# 1591XXM-RS485_to_Neopixel_with_RJ45.net
KiCad netlist of a schematic drawn in EAGLE
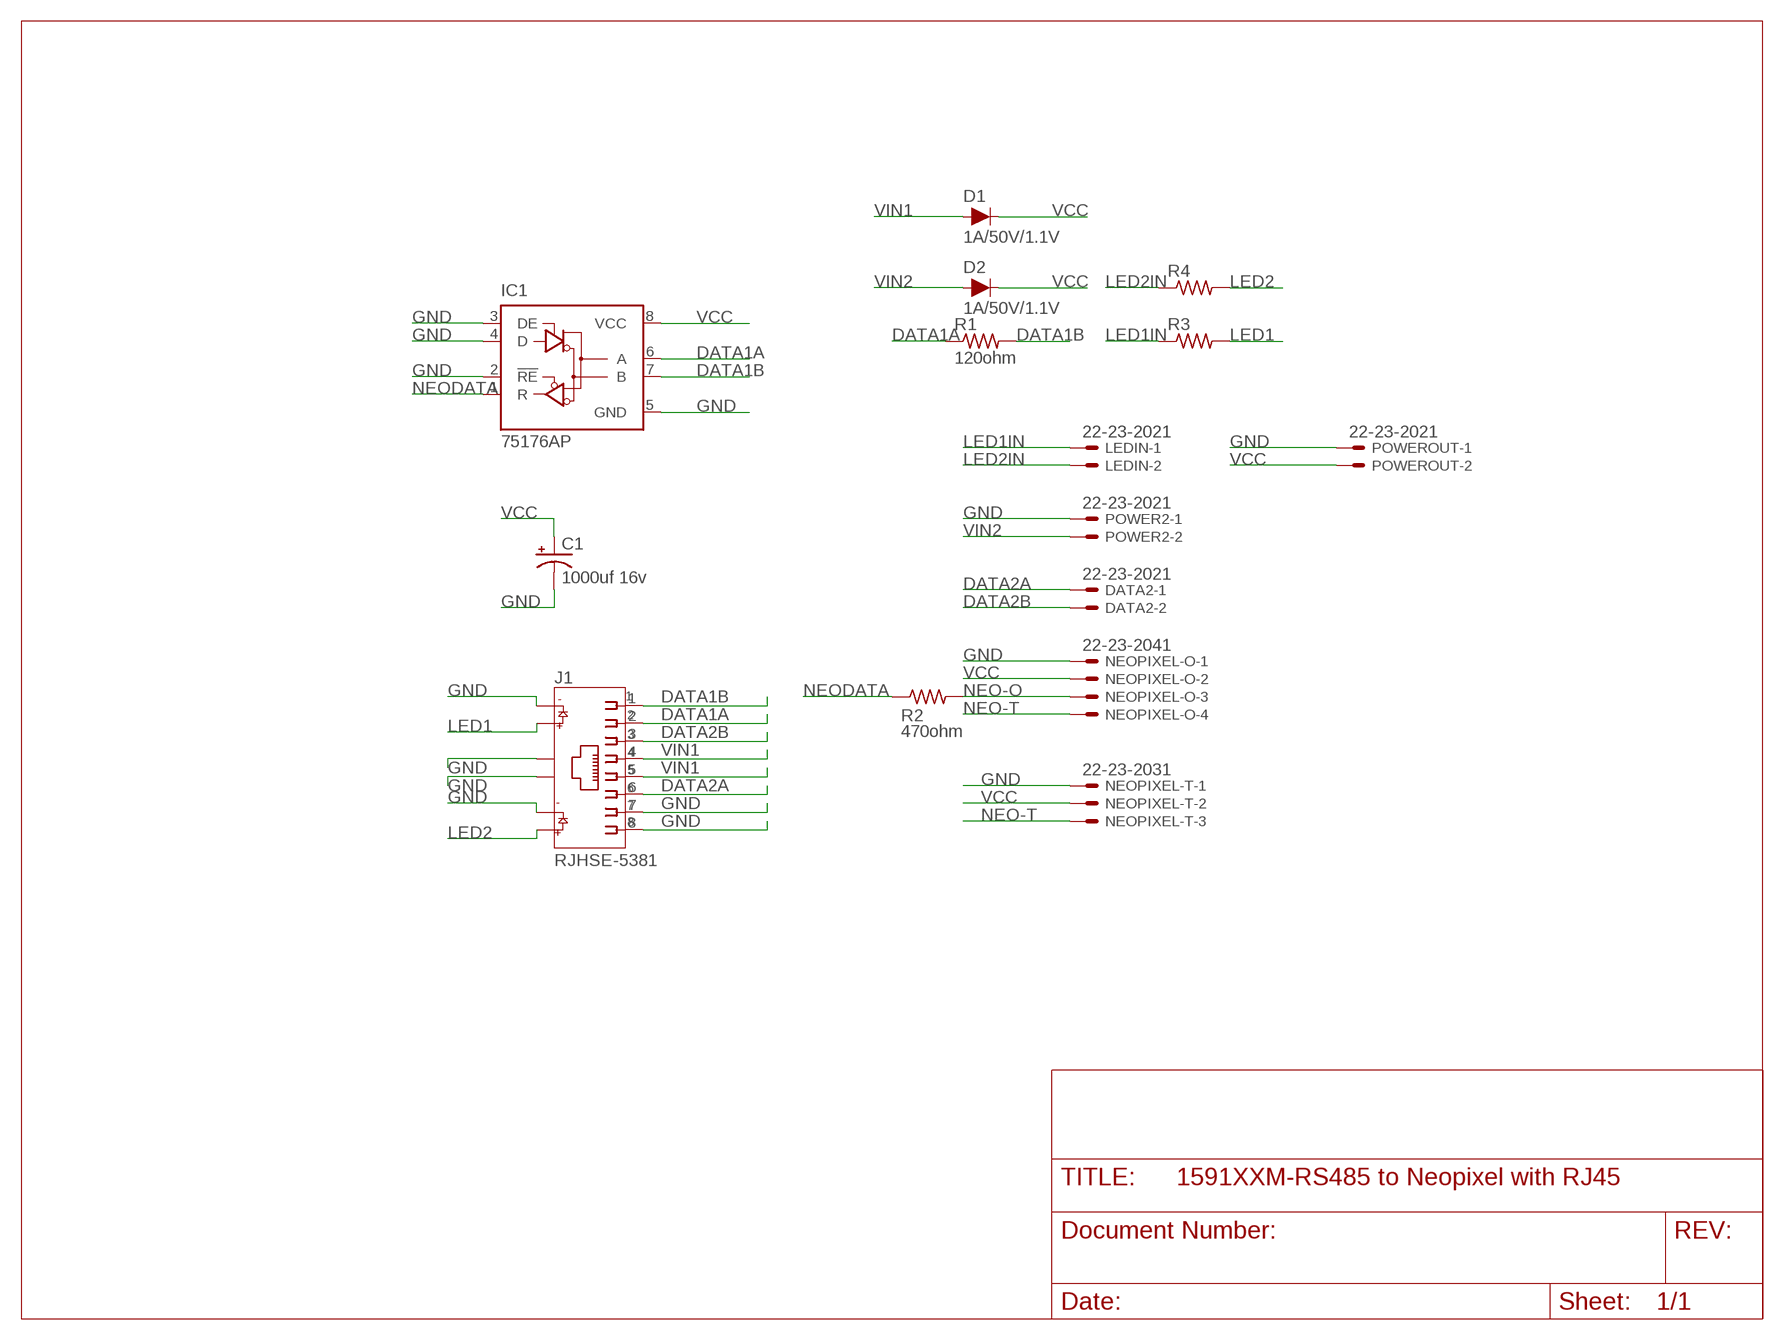
[diagram p0: schematic, sheet 1]

(export (version "E")
  (design (tool "Eeschema 10.0.6"))
  (components
    (comp (ref "C1")
      (value "1000uf 16v")
      (footprint "eagle-import:CPOL-RADIAL-5MM-10MM")
      (libsource (lib "eagle-import") (part "1000UF-RADIAL-5MM-25V-20%"))
    )
    (comp (ref "D1")
      (value "1A/50V/1.1V")
      (footprint "eagle-import:DIODE-1N4001")
      (libsource (lib "eagle-import") (part "DIODE-PTH"))
    )
    (comp (ref "D2")
      (value "1A/50V/1.1V")
      (footprint "eagle-import:DIODE-1N4001")
      (libsource (lib "eagle-import") (part "DIODE-PTH"))
    )
    (comp (ref "DATA2")
      (value "22-23-2021")
      (footprint "eagle-import:22-23-2021")
      (fields (field (name "MF") "MOLEX"))
      (libsource (lib "eagle-import") (part "22-23-2021"))
    )
    (comp (ref "IC1")
      (value "75176AP")
      (footprint "eagle-import:DIL08")
      (libsource (lib "eagle-import") (part "75176AP"))
    )
    (comp (ref "J1")
      (value "RJHSE-5381")
      (footprint "eagle-import:AMPHENOL_RJHSE-5381")
      (fields (field (name "MF") "Amphenol ICC"))
      (libsource (lib "eagle-import") (part "RJHSE-5381"))
    )
    (comp (ref "LEDIN")
      (value "22-23-2021")
      (footprint "eagle-import:22-23-2021")
      (fields (field (name "MF") "MOLEX"))
      (libsource (lib "eagle-import") (part "22-23-2021"))
    )
    (comp (ref "NEOPIXEL-O")
      (value "22-23-2041")
      (footprint "eagle-import:22-23-2041")
      (fields (field (name "MF") "MOLEX"))
      (libsource (lib "eagle-import") (part "22-23-2041"))
    )
    (comp (ref "NEOPIXEL-T")
      (value "22-23-2031")
      (footprint "eagle-import:22-23-2031")
      (fields (field (name "MF") "MOLEX"))
      (libsource (lib "eagle-import") (part "22-23-2031"))
    )
    (comp (ref "POWER2")
      (value "22-23-2021")
      (footprint "eagle-import:22-23-2021")
      (fields (field (name "MF") "MOLEX"))
      (libsource (lib "eagle-import") (part "22-23-2021"))
    )
    (comp (ref "POWEROUT")
      (value "22-23-2021")
      (footprint "eagle-import:22-23-2021")
      (fields (field (name "MF") "MOLEX"))
      (libsource (lib "eagle-import") (part "22-23-2021"))
    )
    (comp (ref "R1")
      (value "120ohm")
      (footprint "eagle-import:0207_10")
      (libsource (lib "eagle-import") (part "R-US_0207/10"))
    )
    (comp (ref "R2")
      (value "470ohm")
      (footprint "eagle-import:0207_10")
      (libsource (lib "eagle-import") (part "R-US_0207/10"))
    )
    (comp (ref "R3")
      (value "R-US_0207/10")
      (footprint "eagle-import:0207_10")
      (libsource (lib "eagle-import") (part "R-US_0207/10"))
    )
    (comp (ref "R4")
      (value "R-US_0207/10")
      (footprint "eagle-import:0207_10")
      (libsource (lib "eagle-import") (part "R-US_0207/10"))
    )
  )
  (nets
    (net (code "1") (name "/DATA1A") (class "Default")
      (node (ref "IC1") (pin "6") (pinfunction "A_6") (pintype "output"))
      (node (ref "J1") (pin "2") (pinfunction "2_2") (pintype "passive"))
      (node (ref "R1") (pin "1") (pinfunction "1_1") (pintype "passive"))
    )
    (net (code "2") (name "/DATA1B") (class "Default")
      (node (ref "IC1") (pin "7") (pinfunction "B_7") (pintype "output"))
      (node (ref "J1") (pin "1") (pinfunction "1_1") (pintype "passive"))
      (node (ref "R1") (pin "2") (pinfunction "2_2") (pintype "passive"))
    )
    (net (code "3") (name "/DATA2A") (class "Default")
      (node (ref "DATA2") (pin "1") (pinfunction "S_1") (pintype "passive"))
      (node (ref "J1") (pin "6") (pinfunction "6_6") (pintype "passive"))
    )
    (net (code "4") (name "/DATA2B") (class "Default")
      (node (ref "DATA2") (pin "2") (pinfunction "S_2") (pintype "passive"))
      (node (ref "J1") (pin "3") (pinfunction "3_3") (pintype "passive"))
    )
    (net (code "5") (name "/GND") (class "Default")
      (node (ref "C1") (pin "-") (pinfunction "-_-") (pintype "passive"))
      (node (ref "IC1") (pin "2") (pinfunction "~{RE}_2") (pintype "input"))
      (node (ref "IC1") (pin "3") (pinfunction "DE_3") (pintype "input"))
      (node (ref "IC1") (pin "4") (pinfunction "D_4") (pintype "input"))
      (node (ref "IC1") (pin "5") (pinfunction "GND_5") (pintype "power_in"))
      (node (ref "J1") (pin "11") (pinfunction "11_11") (pintype "passive"))
      (node (ref "J1") (pin "7") (pinfunction "7_7") (pintype "passive"))
      (node (ref "J1") (pin "8") (pinfunction "8_8") (pintype "passive"))
      (node (ref "J1") (pin "9") (pinfunction "9_9") (pintype "passive"))
      (node (ref "J1") (pin "S1") (pinfunction "S1_S1") (pintype "passive"))
      (node (ref "J1") (pin "S2") (pinfunction "S2_S2") (pintype "passive"))
      (node (ref "NEOPIXEL-O") (pin "1") (pinfunction "S_1") (pintype "passive"))
      (node (ref "NEOPIXEL-T") (pin "1") (pinfunction "S_1") (pintype "passive"))
      (node (ref "POWER2") (pin "1") (pinfunction "S_1") (pintype "passive"))
      (node (ref "POWEROUT") (pin "1") (pinfunction "S_1") (pintype "passive"))
    )
    (net (code "6") (name "/LED1") (class "Default")
      (node (ref "J1") (pin "10") (pinfunction "10_10") (pintype "passive"))
      (node (ref "R3") (pin "2") (pinfunction "2_2") (pintype "passive"))
    )
    (net (code "7") (name "/LED1IN") (class "Default")
      (node (ref "LEDIN") (pin "1") (pinfunction "S_1") (pintype "passive"))
      (node (ref "R3") (pin "1") (pinfunction "1_1") (pintype "passive"))
    )
    (net (code "8") (name "/LED2") (class "Default")
      (node (ref "J1") (pin "12") (pinfunction "12_12") (pintype "passive"))
      (node (ref "R4") (pin "2") (pinfunction "2_2") (pintype "passive"))
    )
    (net (code "9") (name "/LED2IN") (class "Default")
      (node (ref "LEDIN") (pin "2") (pinfunction "S_2") (pintype "passive"))
      (node (ref "R4") (pin "1") (pinfunction "1_1") (pintype "passive"))
    )
    (net (code "10") (name "/NEO-O") (class "Default")
      (node (ref "NEOPIXEL-O") (pin "3") (pinfunction "S_3") (pintype "passive"))
      (node (ref "R2") (pin "2") (pinfunction "2_2") (pintype "passive"))
    )
    (net (code "11") (name "/NEO-T") (class "Default")
      (node (ref "NEOPIXEL-O") (pin "4") (pinfunction "S_4") (pintype "passive"))
      (node (ref "NEOPIXEL-T") (pin "3") (pinfunction "S_3") (pintype "passive"))
    )
    (net (code "12") (name "/NEODATA") (class "Default")
      (node (ref "IC1") (pin "1") (pinfunction "R_1") (pintype "input"))
      (node (ref "R2") (pin "1") (pinfunction "1_1") (pintype "passive"))
    )
    (net (code "13") (name "/VCC") (class "Default")
      (node (ref "C1") (pin "+") (pinfunction "+_+") (pintype "passive"))
      (node (ref "D1") (pin "C") (pinfunction "C_C") (pintype "passive"))
      (node (ref "D2") (pin "C") (pinfunction "C_C") (pintype "passive"))
      (node (ref "IC1") (pin "8") (pinfunction "VCC_8") (pintype "power_in"))
      (node (ref "NEOPIXEL-O") (pin "2") (pinfunction "S_2") (pintype "passive"))
      (node (ref "NEOPIXEL-T") (pin "2") (pinfunction "S_2") (pintype "passive"))
      (node (ref "POWEROUT") (pin "2") (pinfunction "S_2") (pintype "passive"))
    )
    (net (code "14") (name "/VIN1") (class "Default")
      (node (ref "D1") (pin "A") (pinfunction "A_A") (pintype "passive"))
      (node (ref "J1") (pin "4") (pinfunction "4_4") (pintype "passive"))
      (node (ref "J1") (pin "5") (pinfunction "5_5") (pintype "passive"))
    )
    (net (code "15") (name "/VIN2") (class "Default")
      (node (ref "D2") (pin "A") (pinfunction "A_A") (pintype "passive"))
      (node (ref "POWER2") (pin "2") (pinfunction "S_2") (pintype "passive"))
    )
  )
)
